# VM_Motor_v07.net
KiCad netlist of a schematic drawn in EAGLE
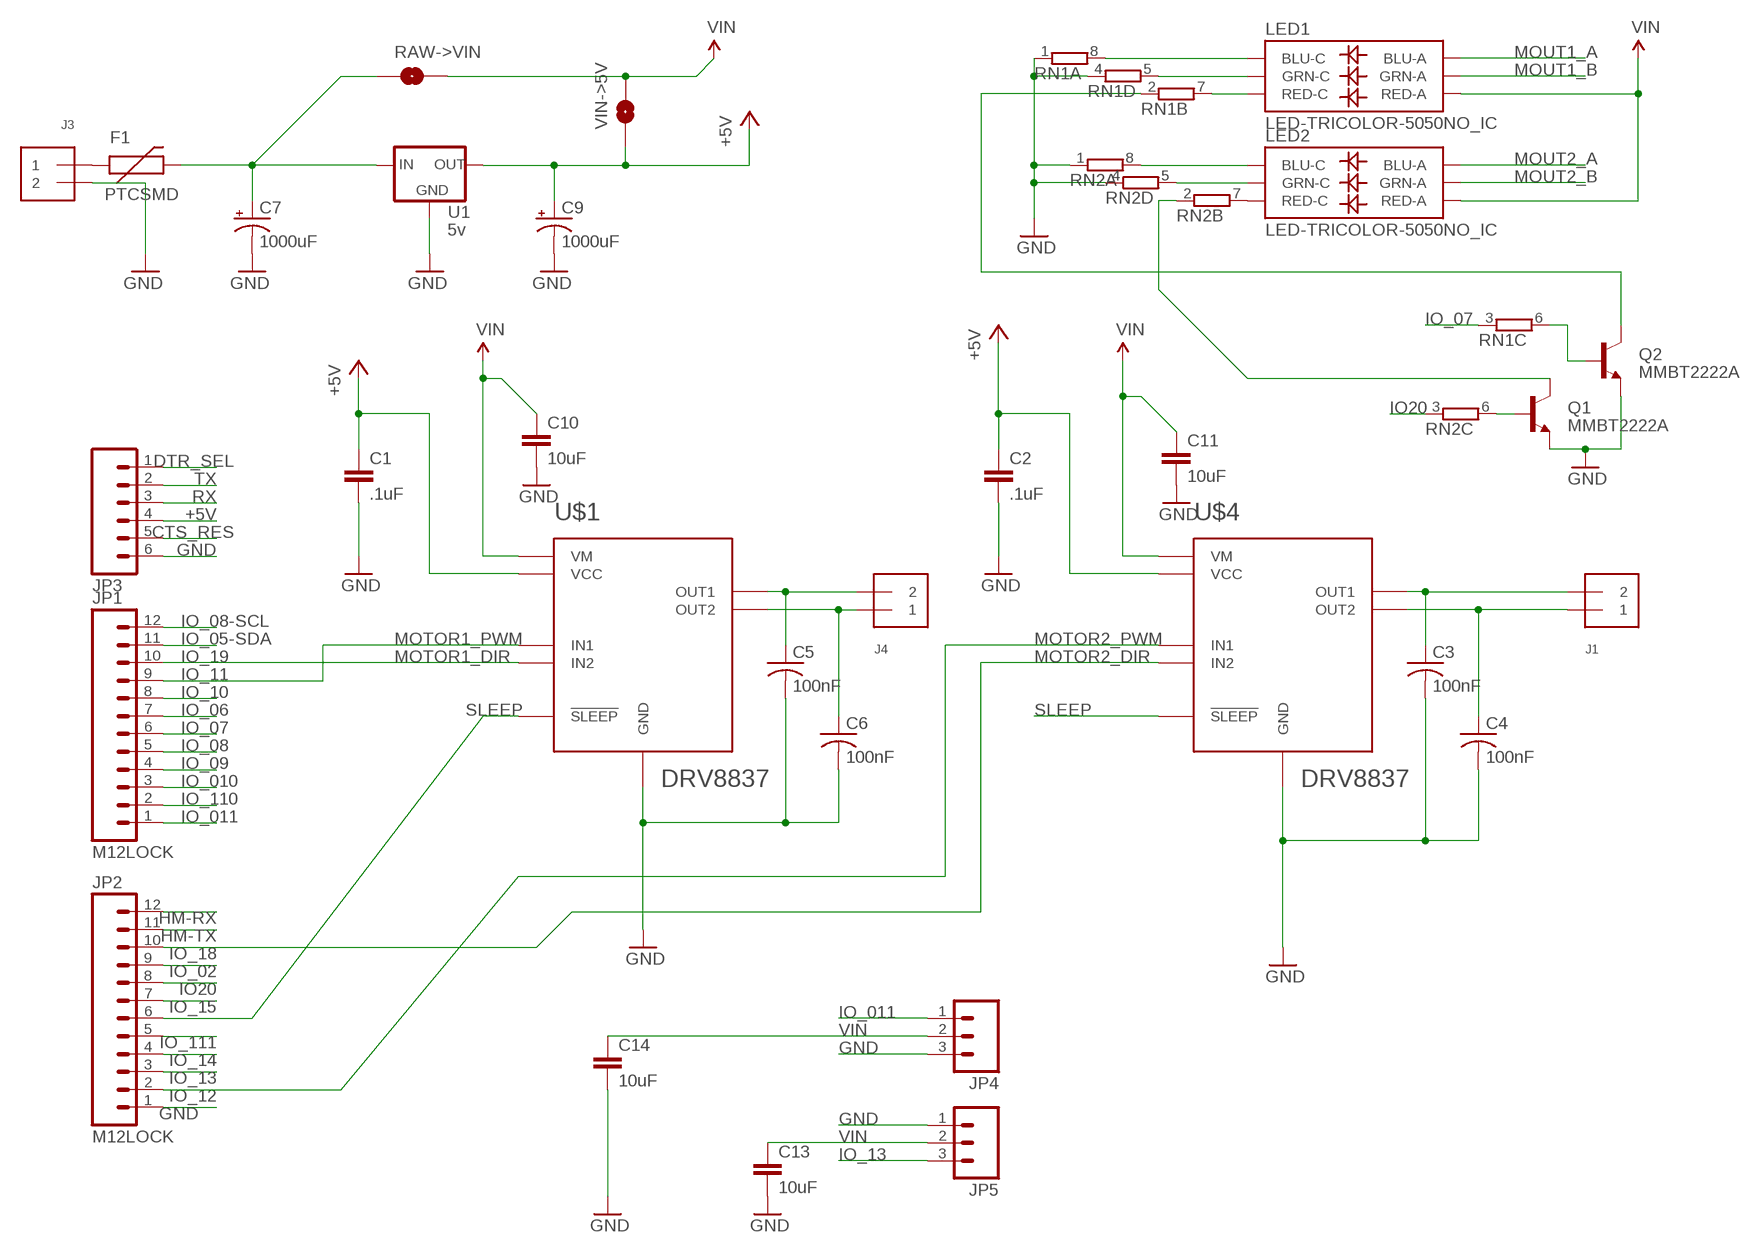
[diagram p0: schematic, sheet 1]

(export (version "E")
  (design (tool "Eeschema 10.0.6"))
  (components
    (comp (ref "C1")
      (value ".1uF")
      (footprint "eagle-import:0402-CAP")
      (libsource (lib "eagle-import") (part "CAP0402-CAP"))
    )
    (comp (ref "C2")
      (value ".1uF")
      (footprint "eagle-import:0402-CAP")
      (libsource (lib "eagle-import") (part "CAP0402-CAP"))
    )
    (comp (ref "C3")
      (value "100nF")
      (footprint "eagle-import:C0402")
      (libsource (lib "eagle-import") (part "C-USC0402"))
    )
    (comp (ref "C4")
      (value "100nF")
      (footprint "eagle-import:C0402")
      (libsource (lib "eagle-import") (part "C-USC0402"))
    )
    (comp (ref "C5")
      (value "100nF")
      (footprint "eagle-import:C0402")
      (libsource (lib "eagle-import") (part "C-USC0402"))
    )
    (comp (ref "C6")
      (value "100nF")
      (footprint "eagle-import:C0402")
      (libsource (lib "eagle-import") (part "C-USC0402"))
    )
    (comp (ref "C7")
      (value "1000uF")
      (footprint "eagle-import:150CLZ-0810")
      (libsource (lib "eagle-import") (part "CPOL-US150CLZ-0810"))
    )
    (comp (ref "C9")
      (value "1000uF")
      (footprint "eagle-import:150CLZ-0810")
      (libsource (lib "eagle-import") (part "CPOL-US150CLZ-0810"))
    )
    (comp (ref "C10")
      (value "10uF")
      (footprint "eagle-import:0402-CAP")
      (libsource (lib "eagle-import") (part "CAP0402-CAP"))
    )
    (comp (ref "C11")
      (value "10uF")
      (footprint "eagle-import:0402-CAP")
      (libsource (lib "eagle-import") (part "CAP0402-CAP"))
    )
    (comp (ref "C13")
      (value "10uF")
      (footprint "eagle-import:0402-CAP")
      (libsource (lib "eagle-import") (part "CAP0402-CAP"))
    )
    (comp (ref "C14")
      (value "10uF")
      (footprint "eagle-import:0402-CAP")
      (libsource (lib "eagle-import") (part "CAP0402-CAP"))
    )
    (comp (ref "F1")
      (value "PTCSMD")
      (footprint "eagle-import:PTC-1206")
      (libsource (lib "eagle-import") (part "PTCSMD"))
    )
    (comp (ref "J1")
      (value "TERMBLOCK_1X2")
      (footprint "eagle-import:TERMBLOCK_1X2-3.5MM")
      (libsource (lib "eagle-import") (part "TERMBLOCK_1X2"))
    )
    (comp (ref "J3")
      (value "TERMBLOCK_1X2")
      (footprint "eagle-import:TERMBLOCK_1X2-3.5MM")
      (libsource (lib "eagle-import") (part "TERMBLOCK_1X2"))
    )
    (comp (ref "J4")
      (value "TERMBLOCK_1X2")
      (footprint "eagle-import:TERMBLOCK_1X2-3.5MM")
      (libsource (lib "eagle-import") (part "TERMBLOCK_1X2"))
    )
    (comp (ref "JP1")
      (value "M12LOCK")
      (footprint "eagle-import:1X12_LOCK")
      (libsource (lib "eagle-import") (part "M12LOCK"))
    )
    (comp (ref "JP2")
      (value "M12LOCK")
      (footprint "eagle-import:1X12_LOCK")
      (libsource (lib "eagle-import") (part "M12LOCK"))
    )
    (comp (ref "JP3")
      (value "M06LOCK")
      (footprint "eagle-import:1X06_LOCK")
      (libsource (lib "eagle-import") (part "M06LOCK"))
    )
    (comp (ref "JP4")
      (value "M03LOCK")
      (footprint "eagle-import:1X03_LOCK")
      (libsource (lib "eagle-import") (part "M03LOCK"))
    )
    (comp (ref "JP5")
      (value "M03LOCK")
      (footprint "eagle-import:1X03_LOCK")
      (libsource (lib "eagle-import") (part "M03LOCK"))
    )
    (comp (ref "LED1")
      (value "LED-TRICOLOR-5050NO_IC")
      (footprint "eagle-import:LED-TRICOLOR-5050")
      (libsource (lib "eagle-import") (part "LED-TRICOLOR-5050NO_IC"))
    )
    (comp (ref "LED2")
      (value "LED-TRICOLOR-5050NO_IC")
      (footprint "eagle-import:LED-TRICOLOR-5050")
      (libsource (lib "eagle-import") (part "LED-TRICOLOR-5050NO_IC"))
    )
    (comp (ref "Q1")
      (value "MMBT2222A")
      (footprint "eagle-import:SOT23-3")
      (libsource (lib "eagle-import") (part "TRANSISTOR_NPNMMBT2222A"))
    )
    (comp (ref "Q2")
      (value "MMBT2222A")
      (footprint "eagle-import:SOT23-3")
      (libsource (lib "eagle-import") (part "TRANSISTOR_NPNMMBT2222A"))
    )
    (comp (ref "RAW->VIN")
      (value "SOLDERJUMPERNO")
      (footprint "eagle-import:SJ_2S-NO")
      (libsource (lib "eagle-import") (part "SOLDERJUMPERNO"))
    )
    (comp (ref "RN1")
      (value "4R-N0402ARV341")
      (footprint "eagle-import:4X0402ARV341")
      (libsource (lib "eagle-import") (part "4R-N0402ARV341"))
    )
    (comp (ref "RN2")
      (value "4R-N0402ARV341")
      (footprint "eagle-import:4X0402ARV341")
      (libsource (lib "eagle-import") (part "4R-N0402ARV341"))
    )
    (comp (ref "U$1")
      (value "DRV8837")
      (footprint "eagle-import:QFN8")
      (libsource (lib "eagle-import") (part "DRV8837"))
    )
    (comp (ref "U$4")
      (value "DRV8837")
      (footprint "eagle-import:QFN8")
      (libsource (lib "eagle-import") (part "DRV8837"))
    )
    (comp (ref "U1")
      (value "5v")
      (footprint "eagle-import:DPAK")
      (libsource (lib "eagle-import") (part "V_REG_MC33269DT"))
    )
    (comp (ref "VIN->5V")
      (value "SOLDERJUMPERNO")
      (footprint "eagle-import:SJ_2S-NO")
      (libsource (lib "eagle-import") (part "SOLDERJUMPERNO"))
    )
  )
  (nets
    (net (code "1") (name "+5V") (class "Default")
      (node (ref "C1") (pin "1") (pinfunction "1_1") (pintype "passive"))
      (node (ref "C2") (pin "1") (pinfunction "1_1") (pintype "passive"))
      (node (ref "C9") (pin "+") (pinfunction "+_+") (pintype "passive"))
      (node (ref "JP3") (pin "4") (pinfunction "4_4") (pintype "passive"))
      (node (ref "U$1") (pin "P$8") (pinfunction "VCC_P$8") (pintype "bidirectional"))
      (node (ref "U$4") (pin "P$8") (pinfunction "VCC_P$8") (pintype "bidirectional"))
      (node (ref "U1") (pin "4") (pinfunction "OUT_4") (pintype "output"))
      (node (ref "VIN->5V") (pin "1") (pinfunction "1_1") (pintype "passive"))
    )
    (net (code "2") (name "/CTS_RES") (class "Default")
      (node (ref "JP3") (pin "5") (pinfunction "5_5") (pintype "passive"))
    )
    (net (code "3") (name "/DTR_SEL") (class "Default")
      (node (ref "JP3") (pin "1") (pinfunction "1_1") (pintype "passive"))
    )
    (net (code "4") (name "/HM-RX") (class "Default")
      (node (ref "JP2") (pin "12") (pinfunction "12_12") (pintype "passive"))
    )
    (net (code "5") (name "/HM-TX") (class "Default")
      (node (ref "JP2") (pin "11") (pinfunction "11_11") (pintype "passive"))
    )
    (net (code "6") (name "/IO20") (class "Default")
      (node (ref "JP2") (pin "8") (pinfunction "8_8") (pintype "passive"))
      (node (ref "RN2") (pin "3") (pinfunction "1_3") (pintype "passive"))
    )
    (net (code "7") (name "/IO_02") (class "Default")
      (node (ref "JP2") (pin "9") (pinfunction "9_9") (pintype "passive"))
    )
    (net (code "8") (name "/IO_05-SDA") (class "Default")
      (node (ref "JP1") (pin "11") (pinfunction "11_11") (pintype "passive"))
    )
    (net (code "9") (name "/IO_06") (class "Default")
      (node (ref "JP1") (pin "7") (pinfunction "7_7") (pintype "passive"))
    )
    (net (code "10") (name "/IO_07") (class "Default")
      (node (ref "JP1") (pin "6") (pinfunction "6_6") (pintype "passive"))
      (node (ref "RN1") (pin "3") (pinfunction "1_3") (pintype "passive"))
    )
    (net (code "11") (name "/IO_08") (class "Default")
      (node (ref "JP1") (pin "5") (pinfunction "5_5") (pintype "passive"))
    )
    (net (code "12") (name "/IO_08-SCL") (class "Default")
      (node (ref "JP1") (pin "12") (pinfunction "12_12") (pintype "passive"))
    )
    (net (code "13") (name "/IO_09") (class "Default")
      (node (ref "JP1") (pin "4") (pinfunction "4_4") (pintype "passive"))
    )
    (net (code "14") (name "/IO_10") (class "Default")
      (node (ref "JP1") (pin "8") (pinfunction "8_8") (pintype "passive"))
    )
    (net (code "15") (name "/IO_010") (class "Default")
      (node (ref "JP1") (pin "3") (pinfunction "3_3") (pintype "passive"))
    )
    (net (code "16") (name "/IO_011") (class "Default")
      (node (ref "JP1") (pin "1") (pinfunction "1_1") (pintype "passive"))
      (node (ref "JP4") (pin "1") (pinfunction "1_1") (pintype "passive"))
    )
    (net (code "17") (name "/IO_13") (class "Default")
      (node (ref "JP2") (pin "3") (pinfunction "3_3") (pintype "passive"))
      (node (ref "JP5") (pin "3") (pinfunction "3_3") (pintype "passive"))
    )
    (net (code "18") (name "/IO_14") (class "Default")
      (node (ref "JP2") (pin "4") (pinfunction "4_4") (pintype "passive"))
    )
    (net (code "19") (name "/IO_15") (class "Default")
      (node (ref "JP2") (pin "7") (pinfunction "7_7") (pintype "passive"))
    )
    (net (code "20") (name "/IO_110") (class "Default")
      (node (ref "JP1") (pin "2") (pinfunction "2_2") (pintype "passive"))
    )
    (net (code "21") (name "/IO_111") (class "Default")
      (node (ref "JP2") (pin "5") (pinfunction "5_5") (pintype "passive"))
    )
    (net (code "22") (name "/MOTOR1_DIR") (class "Default")
      (node (ref "JP1") (pin "10") (pinfunction "10_10") (pintype "passive"))
      (node (ref "U$1") (pin "P$5") (pinfunction "IN2_P$5") (pintype "bidirectional"))
    )
    (net (code "23") (name "/MOTOR1_PWM") (class "Default")
      (node (ref "JP1") (pin "9") (pinfunction "9_9") (pintype "passive"))
      (node (ref "U$1") (pin "P$6") (pinfunction "IN1_P$6") (pintype "bidirectional"))
    )
    (net (code "24") (name "/MOTOR2_DIR") (class "Default")
      (node (ref "JP2") (pin "10") (pinfunction "10_10") (pintype "passive"))
      (node (ref "U$4") (pin "P$5") (pinfunction "IN2_P$5") (pintype "bidirectional"))
    )
    (net (code "25") (name "/MOTOR2_PWM") (class "Default")
      (node (ref "JP2") (pin "2") (pinfunction "2_2") (pintype "passive"))
      (node (ref "U$4") (pin "P$6") (pinfunction "IN1_P$6") (pintype "bidirectional"))
    )
    (net (code "26") (name "/MOUT1_A") (class "Default")
      (node (ref "C5") (pin "1") (pinfunction "1_1") (pintype "passive"))
      (node (ref "J4") (pin "2") (pinfunction "2_2") (pintype "passive"))
      (node (ref "LED1") (pin "3") (pinfunction "BLU-A_3") (pintype "bidirectional"))
      (node (ref "U$1") (pin "P$2") (pinfunction "OUT1_P$2") (pintype "bidirectional"))
    )
    (net (code "27") (name "/MOUT1_B") (class "Default")
      (node (ref "C6") (pin "1") (pinfunction "1_1") (pintype "passive"))
      (node (ref "J4") (pin "1") (pinfunction "1_1") (pintype "passive"))
      (node (ref "LED1") (pin "1") (pinfunction "GRN-A_1") (pintype "bidirectional"))
      (node (ref "U$1") (pin "P$3") (pinfunction "OUT2_P$3") (pintype "bidirectional"))
    )
    (net (code "28") (name "/MOUT2_A") (class "Default")
      (node (ref "C3") (pin "1") (pinfunction "1_1") (pintype "passive"))
      (node (ref "J1") (pin "2") (pinfunction "2_2") (pintype "passive"))
      (node (ref "LED2") (pin "3") (pinfunction "BLU-A_3") (pintype "bidirectional"))
      (node (ref "U$4") (pin "P$2") (pinfunction "OUT1_P$2") (pintype "bidirectional"))
    )
    (net (code "29") (name "/MOUT2_B") (class "Default")
      (node (ref "C4") (pin "1") (pinfunction "1_1") (pintype "passive"))
      (node (ref "J1") (pin "1") (pinfunction "1_1") (pintype "passive"))
      (node (ref "LED2") (pin "1") (pinfunction "GRN-A_1") (pintype "bidirectional"))
      (node (ref "U$4") (pin "P$3") (pinfunction "OUT2_P$3") (pintype "bidirectional"))
    )
    (net (code "30") (name "/RX") (class "Default")
      (node (ref "JP3") (pin "3") (pinfunction "3_3") (pintype "passive"))
    )
    (net (code "31") (name "/SLEEP") (class "Default")
      (node (ref "JP2") (pin "6") (pinfunction "6_6") (pintype "passive"))
      (node (ref "U$1") (pin "P$7") (pinfunction "~{SLEEP}_P$7") (pintype "bidirectional"))
      (node (ref "U$4") (pin "P$7") (pinfunction "~{SLEEP}_P$7") (pintype "bidirectional"))
    )
    (net (code "32") (name "/TX") (class "Default")
      (node (ref "JP3") (pin "2") (pinfunction "2_2") (pintype "passive"))
    )
    (net (code "33") (name "GND") (class "Default")
      (node (ref "C1") (pin "2") (pinfunction "2_2") (pintype "passive"))
      (node (ref "C10") (pin "2") (pinfunction "2_2") (pintype "passive"))
      (node (ref "C11") (pin "2") (pinfunction "2_2") (pintype "passive"))
      (node (ref "C13") (pin "2") (pinfunction "2_2") (pintype "passive"))
      (node (ref "C14") (pin "2") (pinfunction "2_2") (pintype "passive"))
      (node (ref "C2") (pin "2") (pinfunction "2_2") (pintype "passive"))
      (node (ref "C3") (pin "2") (pinfunction "2_2") (pintype "passive"))
      (node (ref "C4") (pin "2") (pinfunction "2_2") (pintype "passive"))
      (node (ref "C5") (pin "2") (pinfunction "2_2") (pintype "passive"))
      (node (ref "C6") (pin "2") (pinfunction "2_2") (pintype "passive"))
      (node (ref "C7") (pin "-") (pinfunction "-_-") (pintype "passive"))
      (node (ref "C9") (pin "-") (pinfunction "-_-") (pintype "passive"))
      (node (ref "J3") (pin "2") (pinfunction "2_2") (pintype "passive"))
      (node (ref "JP2") (pin "1") (pinfunction "1_1") (pintype "passive"))
      (node (ref "JP3") (pin "6") (pinfunction "6_6") (pintype "passive"))
      (node (ref "JP4") (pin "3") (pinfunction "3_3") (pintype "passive"))
      (node (ref "JP5") (pin "1") (pinfunction "1_1") (pintype "passive"))
      (node (ref "Q1") (pin "2") (pinfunction "E_2") (pintype "passive"))
      (node (ref "Q2") (pin "2") (pinfunction "E_2") (pintype "passive"))
      (node (ref "RN1") (pin "1") (pinfunction "1_1") (pintype "passive"))
      (node (ref "RN1") (pin "4") (pinfunction "1_4") (pintype "passive"))
      (node (ref "RN2") (pin "1") (pinfunction "1_1") (pintype "passive"))
      (node (ref "RN2") (pin "4") (pinfunction "1_4") (pintype "passive"))
      (node (ref "U$1") (pin "P$10") (pinfunction "GND_P$10") (pintype "bidirectional"))
      (node (ref "U$1") (pin "P$11") (pinfunction "GND_P$11") (pintype "bidirectional"))
      (node (ref "U$1") (pin "P$4") (pinfunction "GND_P$4") (pintype "bidirectional"))
      (node (ref "U$1") (pin "P$9") (pinfunction "GND_P$9") (pintype "bidirectional"))
      (node (ref "U$4") (pin "P$10") (pinfunction "GND_P$10") (pintype "bidirectional"))
      (node (ref "U$4") (pin "P$11") (pinfunction "GND_P$11") (pintype "bidirectional"))
      (node (ref "U$4") (pin "P$4") (pinfunction "GND_P$4") (pintype "bidirectional"))
      (node (ref "U$4") (pin "P$9") (pinfunction "GND_P$9") (pintype "bidirectional"))
      (node (ref "U1") (pin "1") (pinfunction "GND_1") (pintype "input"))
    )
    (net (code "34") (name "Net-(F1-Pad1)") (class "Default")
      (node (ref "F1") (pin "1") (pinfunction "1_1") (pintype "bidirectional"))
      (node (ref "J3") (pin "1") (pinfunction "1_1") (pintype "passive"))
    )
    (net (code "35") (name "Net-(LED1-BLU-C)") (class "Default")
      (node (ref "LED1") (pin "4") (pinfunction "BLU-C_4") (pintype "bidirectional"))
      (node (ref "RN1") (pin "8") (pinfunction "2_8") (pintype "passive"))
    )
    (net (code "36") (name "Net-(LED1-GRN-C)") (class "Default")
      (node (ref "LED1") (pin "6") (pinfunction "GRN-C_6") (pintype "bidirectional"))
      (node (ref "RN1") (pin "5") (pinfunction "2_5") (pintype "passive"))
    )
    (net (code "37") (name "Net-(LED1-RED-C)") (class "Default")
      (node (ref "LED1") (pin "5") (pinfunction "RED-C_5") (pintype "bidirectional"))
      (node (ref "RN1") (pin "7") (pinfunction "2_7") (pintype "passive"))
    )
    (net (code "38") (name "Net-(LED2-BLU-C)") (class "Default")
      (node (ref "LED2") (pin "4") (pinfunction "BLU-C_4") (pintype "bidirectional"))
      (node (ref "RN2") (pin "8") (pinfunction "2_8") (pintype "passive"))
    )
    (net (code "39") (name "Net-(LED2-GRN-C)") (class "Default")
      (node (ref "LED2") (pin "6") (pinfunction "GRN-C_6") (pintype "bidirectional"))
      (node (ref "RN2") (pin "5") (pinfunction "2_5") (pintype "passive"))
    )
    (net (code "40") (name "Net-(LED2-RED-C)") (class "Default")
      (node (ref "LED2") (pin "5") (pinfunction "RED-C_5") (pintype "bidirectional"))
      (node (ref "RN2") (pin "7") (pinfunction "2_7") (pintype "passive"))
    )
    (net (code "41") (name "Net-(Q1-B)") (class "Default")
      (node (ref "Q1") (pin "1") (pinfunction "B_1") (pintype "passive"))
      (node (ref "RN2") (pin "6") (pinfunction "2_6") (pintype "passive"))
    )
    (net (code "42") (name "Net-(Q1-C)") (class "Default")
      (node (ref "Q1") (pin "3") (pinfunction "C_3") (pintype "passive"))
      (node (ref "RN2") (pin "2") (pinfunction "1_2") (pintype "passive"))
    )
    (net (code "43") (name "Net-(Q2-B)") (class "Default")
      (node (ref "Q2") (pin "1") (pinfunction "B_1") (pintype "passive"))
      (node (ref "RN1") (pin "6") (pinfunction "2_6") (pintype "passive"))
    )
    (net (code "44") (name "Net-(Q2-C)") (class "Default")
      (node (ref "Q2") (pin "3") (pinfunction "C_3") (pintype "passive"))
      (node (ref "RN1") (pin "2") (pinfunction "1_2") (pintype "passive"))
    )
    (net (code "45") (name "Net-(U1-IN)") (class "Default")
      (node (ref "C7") (pin "+") (pinfunction "+_+") (pintype "passive"))
      (node (ref "F1") (pin "2") (pinfunction "2_2") (pintype "bidirectional"))
      (node (ref "RAW->VIN") (pin "1") (pinfunction "1_1") (pintype "passive"))
      (node (ref "U1") (pin "3") (pinfunction "IN_3") (pintype "input"))
    )
    (net (code "46") (name "VIN") (class "Default")
      (node (ref "C10") (pin "1") (pinfunction "1_1") (pintype "passive"))
      (node (ref "C11") (pin "1") (pinfunction "1_1") (pintype "passive"))
      (node (ref "C13") (pin "1") (pinfunction "1_1") (pintype "passive"))
      (node (ref "C14") (pin "1") (pinfunction "1_1") (pintype "passive"))
      (node (ref "JP4") (pin "2") (pinfunction "2_2") (pintype "passive"))
      (node (ref "JP5") (pin "2") (pinfunction "2_2") (pintype "passive"))
      (node (ref "LED1") (pin "2") (pinfunction "RED-A_2") (pintype "bidirectional"))
      (node (ref "LED2") (pin "2") (pinfunction "RED-A_2") (pintype "bidirectional"))
      (node (ref "RAW->VIN") (pin "2") (pinfunction "2_2") (pintype "passive"))
      (node (ref "U$1") (pin "P$1") (pinfunction "VM_P$1") (pintype "bidirectional"))
      (node (ref "U$4") (pin "P$1") (pinfunction "VM_P$1") (pintype "bidirectional"))
      (node (ref "VIN->5V") (pin "2") (pinfunction "2_2") (pintype "passive"))
    )
  )
)
